# 24V_Supply.net
KiCad netlist of a schematic drawn in Altium Designer
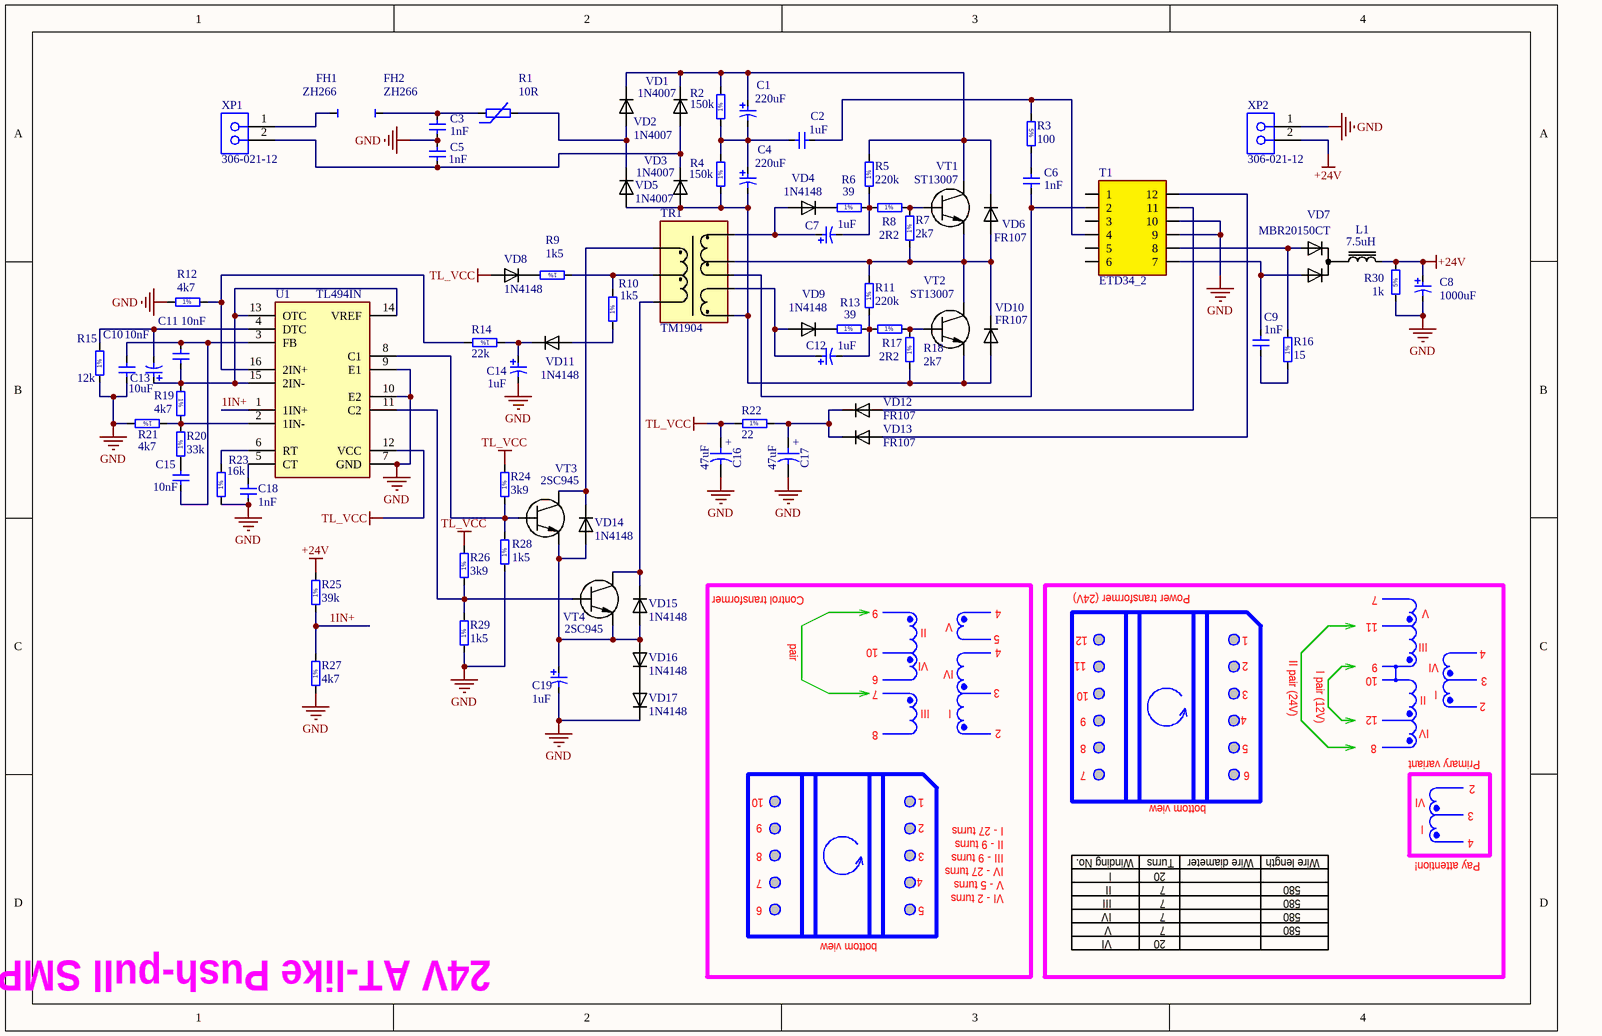
[diagram p0: 24V_Supply.SchDoc]

(export (version "E")
  (design (tool "Eeschema 10.0.6"))
  (components
    (comp (ref "C1")
      (value "220uF")
      (footprint "CAP_EL_22_25_VERT")
      (fields
        (field (name "PART NUMBER") "LG200M0220BPF-2225 (VERT MOUNTED)")
        (field (name "VOLTAGE") "200V")
      )
      (libsource (lib "Capacitor") (part "CAP_POLAR"))
    )
    (comp (ref "C2")
      (value "1uF")
      (footprint "CAPRR2000W80L2400T750H1500_CL21")
      (description "SMD 0805 Capacitor")
      (fields (field (name "PART NUMBER") "К73-17-250-1 10%") (field (name "VOLTAGE") "250V"))
      (libsource (lib "Capacitor") (part "CAP_NON_POLAR"))
    )
    (comp (ref "C3")
      (value "1nF")
      (footprint "CAP_5.0MM")
      (description "SMD 0805 Capacitor")
      (fields (field (name "PART NUMBER") "CK45-B3DD102KYNN") (field (name "VOLTAGE") "2000V"))
      (libsource (lib "Capacitor") (part "CAP_NON_POLAR"))
    )
    (comp (ref "C4")
      (value "220uF")
      (footprint "CAP_EL_22_25_VERT")
      (fields
        (field (name "PART NUMBER") "LG200M0220BPF-2225 (VERT MOUNTED)")
        (field (name "VOLTAGE") "200V")
      )
      (libsource (lib "Capacitor") (part "CAP_POLAR"))
    )
    (comp (ref "C5")
      (value "1nF")
      (footprint "CAP_5.0MM")
      (description "SMD 0805 Capacitor")
      (fields (field (name "PART NUMBER") "CK45-B3DD102KYNN") (field (name "VOLTAGE") "2000V"))
      (libsource (lib "Capacitor") (part "CAP_NON_POLAR"))
    )
    (comp (ref "C6")
      (value "1nF")
      (footprint "CAP_5.0MM")
      (description "SMD 0805 Capacitor")
      (fields (field (name "PART NUMBER") "CK45-B3DD102KYNN") (field (name "VOLTAGE") "2000V"))
      (libsource (lib "Capacitor") (part "CAP_NON_POLAR"))
    )
    (comp (ref "C7")
      (value "1uF")
      (footprint "CAP_EL_05_11_VERT")
      (fields (field (name "PART NUMBER") "SH050M1R00B2F-0511 (VERT MOUNTED)") (field (name "VOLTAGE") "50V"))
      (libsource (lib "Capacitor") (part "CAP_POLAR"))
    )
    (comp (ref "C8")
      (value "1000uF")
      (footprint "CAP_EL_13_20_VERT")
      (fields (field (name "PART NUMBER") "SK035M1000B5S-1320 (VERT MOUNTED)") (field (name "VOLTAGE") "35V"))
      (libsource (lib "Capacitor") (part "CAP_POLAR"))
    )
    (comp (ref "C9")
      (value "1nF")
      (footprint "CAP_5.0MM")
      (description "SMD 0805 Capacitor")
      (fields (field (name "PART NUMBER") "CK45-B3DD102KYNN") (field (name "VOLTAGE") "2000V"))
      (libsource (lib "Capacitor") (part "CAP_NON_POLAR"))
    )
    (comp (ref "C10")
      (value "10nF")
      (footprint "CAP_5.0MM")
      (description "SMD 0805 Capacitor")
      (fields (field (name "PART NUMBER") "TS170R1H103K8BBB0R") (field (name "VOLTAGE") "50V"))
      (libsource (lib "Capacitor") (part "CAP_NON_POLAR"))
    )
    (comp (ref "C11")
      (value "10nF")
      (footprint "CAP_5.0MM")
      (description "SMD 0805 Capacitor")
      (fields (field (name "PART NUMBER") "TS170R1H103K8BBB0R") (field (name "VOLTAGE") "50V"))
      (libsource (lib "Capacitor") (part "CAP_NON_POLAR"))
    )
    (comp (ref "C12")
      (value "1uF")
      (footprint "CAP_EL_05_11_VERT")
      (fields (field (name "PART NUMBER") "SH050M1R00B2F-0511 (VERT MOUNTED)") (field (name "VOLTAGE") "50V"))
      (libsource (lib "Capacitor") (part "CAP_POLAR"))
    )
    (comp (ref "C13")
      (value "10uF")
      (footprint "CAP_EL_05_11_VERT")
      (fields (field (name "PART NUMBER") "SH050M0010B2F-0511 (VERT MOUNTED)") (field (name "VOLTAGE") "50V"))
      (libsource (lib "Capacitor") (part "CAP_POLAR"))
    )
    (comp (ref "C14")
      (value "1uF")
      (footprint "CAP_EL_05_11_VERT")
      (fields (field (name "PART NUMBER") "SH050M1R00B2F-0511 (VERT MOUNTED)") (field (name "VOLTAGE") "50V"))
      (libsource (lib "Capacitor") (part "CAP_POLAR"))
    )
    (comp (ref "C15")
      (value "10nF")
      (footprint "CAP_5.0MM")
      (description "SMD 0805 Capacitor")
      (fields (field (name "PART NUMBER") "TS170R1H103K8BBB0R") (field (name "VOLTAGE") "50V"))
      (libsource (lib "Capacitor") (part "CAP_NON_POLAR"))
    )
    (comp (ref "C16")
      (value "47uF")
      (footprint "CAPPR250-500X1100")
      (description "Polarised capacitor")
      (fields
        (field (name "PART NUMBER") "CAER_47UF_25V_20%_250-500X1100")
        (field (name "VOLTAGE") "25V")
        (field (name "AUTHOR") "CERN DEM JLC")
      )
      (libsource (lib "Capacitors") (part "Capacitor - polarized"))
    )
    (comp (ref "C17")
      (value "47uF")
      (footprint "CAPPR250-500X1100")
      (description "Polarised capacitor")
      (fields
        (field (name "PART NUMBER") "CAER_47UF_25V_20%_250-500X1100")
        (field (name "VOLTAGE") "25V")
        (field (name "AUTHOR") "CERN DEM JLC")
      )
      (libsource (lib "Capacitors") (part "Capacitor - polarized"))
    )
    (comp (ref "C18")
      (value "1nF")
      (footprint "CAP_5.0MM")
      (description "SMD 0805 Capacitor")
      (fields (field (name "PART NUMBER") "TS170R1H102JSBNB0R") (field (name "VOLTAGE") "50V"))
      (libsource (lib "Capacitor") (part "CAP_NON_POLAR"))
    )
    (comp (ref "C19")
      (value "1uF")
      (footprint "CAP_EL_05_11_VERT")
      (fields (field (name "PART NUMBER") "SH050M1R00B2F-0511 (VERT MOUNTED)") (field (name "VOLTAGE") "50V"))
      (libsource (lib "Capacitor") (part "CAP_POLAR"))
    )
    (comp (ref "FH1") (value "ZH266") (footprint "ZH266") (libsource (lib "Connector") (part "Fuse Clip")))
    (comp (ref "FH2") (value "ZH266") (footprint "ZH266") (libsource (lib "Connector") (part "Fuse Clip")))
    (comp (ref "L1")
      (value "7.5uH")
      (footprint "DGS")
      (fields (field (name "PART NUMBER") "DGS") (field (name "TOLERANCE") "± 10%"))
      (libsource (lib "Transformer") (part "Core_Inductor"))
    )
    (comp (ref "R1")
      (value "10R")
      (footprint "B57164K")
      (fields (field (name "PART NUMBER") "B57164K"))
      (libsource (lib "Resistor") (part "Resistor - Thermo"))
    )
    (comp (ref "R2")
      (value "150k")
      (footprint "RES_AXIAL_0_25_8")
      (fields
        (field (name "PART NUMBER") "RMF_150K_1%_0.6W_50PPM_1016-630X250")
        (field (name "POWER") "0.6W")
        (field (name "TOLERANCE") "±1%")
        (field (name "AUTHOR") "CERN DEM JLC")
      )
      (libsource (lib "Resistor") (part "Resistor - 1%"))
    )
    (comp (ref "R3")
      (value "100")
      (footprint "RES_VERT_2W_5")
      (fields (field (name "PART NUMBER") "RCF_100R_5%_2W_HB"))
      (libsource (lib "Resistor") (part "Resistor - 5%"))
    )
    (comp (ref "R4")
      (value "150k")
      (footprint "RES_AXIAL_0_25_8")
      (fields
        (field (name "PART NUMBER") "RMF_150K_1%_0.6W_50PPM_1016-630X250")
        (field (name "POWER") "0.6W")
        (field (name "TOLERANCE") "±1%")
        (field (name "AUTHOR") "CERN DEM JLC")
      )
      (libsource (lib "Resistor") (part "Resistor - 1%"))
    )
    (comp (ref "R5")
      (value "220k")
      (footprint "RES_AXIAL_0_25_8")
      (fields
        (field (name "PART NUMBER") "RMF_220K_1%_0.6W_50PPM_1016-630X250")
        (field (name "POWER") "0.6W")
        (field (name "TOLERANCE") "±1%")
        (field (name "AUTHOR") "CERN DEM JLC")
      )
      (libsource (lib "Resistor") (part "Resistor - 1%"))
    )
    (comp (ref "R6")
      (value "39")
      (footprint "RES_AXIAL_0_25_8")
      (fields
        (field (name "PART NUMBER") "RMF_39R_1%_0.6W_50PPM_1016-630X250")
        (field (name "POWER") "0.6W")
        (field (name "TOLERANCE") "±1%")
        (field (name "AUTHOR") "CERN DEM JLC")
      )
      (libsource (lib "Resistor") (part "Resistor - 1%"))
    )
    (comp (ref "R7")
      (value "2k7")
      (footprint "RES_AXIAL_0_25_8")
      (fields
        (field (name "PART NUMBER") "RMF_2K7_1%_0.6W_50PPM_1016-630X250")
        (field (name "POWER") "0.6W")
        (field (name "TOLERANCE") "±1%")
        (field (name "AUTHOR") "CERN DEM JLC")
      )
      (libsource (lib "Resistor") (part "Resistor - 1%"))
    )
    (comp (ref "R8")
      (value "2R2")
      (footprint "RES_AXIAL_0_25_8")
      (fields
        (field (name "PART NUMBER") "RMF_2R2_1%_0.6W_50PPM_1016-630X250")
        (field (name "POWER") "0.6W")
        (field (name "TOLERANCE") "±1%")
        (field (name "AUTHOR") "CERN DEM JLC")
      )
      (libsource (lib "Resistor") (part "Resistor - 1%"))
    )
    (comp (ref "R9")
      (value "1k5")
      (footprint "RES_AXIAL_0_25_8")
      (fields
        (field (name "PART NUMBER") "RMF_1K5_1%_0.6W_50PPM_1016-630X250")
        (field (name "POWER") "0.6W")
        (field (name "TOLERANCE") "±1%")
        (field (name "AUTHOR") "CERN DEM JLC")
      )
      (libsource (lib "Resistor") (part "Resistor - 1%"))
    )
    (comp (ref "R10")
      (value "1k5")
      (footprint "RES_AXIAL_0_25_8")
      (fields
        (field (name "PART NUMBER") "RMF_1K5_1%_0.6W_50PPM_1016-630X250")
        (field (name "POWER") "0.6W")
        (field (name "TOLERANCE") "±1%")
        (field (name "AUTHOR") "CERN DEM JLC")
      )
      (libsource (lib "Resistor") (part "Resistor - 1%"))
    )
    (comp (ref "R11")
      (value "220k")
      (footprint "RES_AXIAL_0_25_8")
      (fields
        (field (name "PART NUMBER") "RMF_220K_1%_0.6W_50PPM_1016-630X250")
        (field (name "POWER") "0.6W")
        (field (name "TOLERANCE") "±1%")
        (field (name "AUTHOR") "CERN DEM JLC")
      )
      (libsource (lib "Resistor") (part "Resistor - 1%"))
    )
    (comp (ref "R12")
      (value "4k7")
      (footprint "RES_AXIAL_0_25_8")
      (fields
        (field (name "PART NUMBER") "RMF_4K7_1%_0.6W_50PPM_1016-630X250")
        (field (name "POWER") "0.6W")
        (field (name "TOLERANCE") "±1%")
        (field (name "AUTHOR") "CERN DEM JLC")
      )
      (libsource (lib "Resistor") (part "Resistor - 1%"))
    )
    (comp (ref "R13")
      (value "39")
      (footprint "RES_AXIAL_0_25_8")
      (fields
        (field (name "PART NUMBER") "RMF_39R_1%_0.6W_50PPM_1016-630X250")
        (field (name "POWER") "0.6W")
        (field (name "TOLERANCE") "±1%")
        (field (name "AUTHOR") "CERN DEM JLC")
      )
      (libsource (lib "Resistor") (part "Resistor - 1%"))
    )
    (comp (ref "R14")
      (value "22k")
      (footprint "RES_AXIAL_0_25_8")
      (fields
        (field (name "PART NUMBER") "RMF_22K_1%_0.6W_50PPM_1016-630X250")
        (field (name "POWER") "0.6W")
        (field (name "TOLERANCE") "±1%")
        (field (name "AUTHOR") "CERN DEM JLC")
      )
      (libsource (lib "Resistor") (part "Resistor - 1%"))
    )
    (comp (ref "R15")
      (value "12k")
      (footprint "RES_AXIAL_0_25_8")
      (fields
        (field (name "PART NUMBER") "RMF_12K_1%_0.6W_50PPM_1016-630X250")
        (field (name "POWER") "0.6W")
        (field (name "TOLERANCE") "±1%")
        (field (name "AUTHOR") "CERN DEM JLC")
      )
      (libsource (lib "Resistor") (part "Resistor - 1%"))
    )
    (comp (ref "R16")
      (value "15")
      (footprint "RES_AXIAL_0_25_8")
      (fields
        (field (name "PART NUMBER") "RMF_15R_1%_0.6W_50PPM_1016-630X250")
        (field (name "POWER") "0.6W")
        (field (name "TOLERANCE") "±1%")
        (field (name "AUTHOR") "CERN DEM JLC")
      )
      (libsource (lib "Resistor") (part "Resistor - 1%"))
    )
    (comp (ref "R17")
      (value "2R2")
      (footprint "RES_AXIAL_0_25_8")
      (fields
        (field (name "PART NUMBER") "RMF_2R2_1%_0.6W_50PPM_1016-630X250")
        (field (name "POWER") "0.6W")
        (field (name "TOLERANCE") "±1%")
        (field (name "AUTHOR") "CERN DEM JLC")
      )
      (libsource (lib "Resistor") (part "Resistor - 1%"))
    )
    (comp (ref "R18")
      (value "2k7")
      (footprint "RES_AXIAL_0_25_8")
      (fields
        (field (name "PART NUMBER") "RMF_2K7_1%_0.6W_50PPM_1016-630X250")
        (field (name "POWER") "0.6W")
        (field (name "TOLERANCE") "±1%")
        (field (name "AUTHOR") "CERN DEM JLC")
      )
      (libsource (lib "Resistor") (part "Resistor - 1%"))
    )
    (comp (ref "R19")
      (value "4k7")
      (footprint "RES_AXIAL_0_25_8")
      (fields
        (field (name "PART NUMBER") "RMF_4K7_1%_0.6W_50PPM_1016-630X250")
        (field (name "POWER") "0.6W")
        (field (name "TOLERANCE") "±1%")
        (field (name "AUTHOR") "CERN DEM JLC")
      )
      (libsource (lib "Resistor") (part "Resistor - 1%"))
    )
    (comp (ref "R20")
      (value "33k")
      (footprint "RES_AXIAL_0_25_8")
      (fields
        (field (name "PART NUMBER") "RMF_33K_1%_0.6W_50PPM_1016-630X250")
        (field (name "POWER") "0.6W")
        (field (name "TOLERANCE") "±1%")
        (field (name "AUTHOR") "CERN DEM JLC")
      )
      (libsource (lib "Resistor") (part "Resistor - 1%"))
    )
    (comp (ref "R21")
      (value "4k7")
      (footprint "RES_AXIAL_0_25_8")
      (fields
        (field (name "PART NUMBER") "RMF_4K7_1%_0.6W_50PPM_1016-630X250")
        (field (name "POWER") "0.6W")
        (field (name "TOLERANCE") "±1%")
        (field (name "AUTHOR") "CERN DEM JLC")
      )
      (libsource (lib "Resistor") (part "Resistor - 1%"))
    )
    (comp (ref "R22")
      (value "22")
      (footprint "RES_AXIAL_0_25_8")
      (fields
        (field (name "PART NUMBER") "RMF_22R_1%_0.6W_50PPM_1016-630X250")
        (field (name "POWER") "0.6W")
        (field (name "TOLERANCE") "±1%")
        (field (name "AUTHOR") "CERN DEM JLC")
      )
      (libsource (lib "Resistor") (part "Resistor - 1%"))
    )
    (comp (ref "R23")
      (value "16k")
      (footprint "RES_AXIAL_0_25_8")
      (fields
        (field (name "PART NUMBER") "RMF_16K_1%_0.6W_50PPM_1016-630X250")
        (field (name "POWER") "0.6W")
        (field (name "TOLERANCE") "±1%")
        (field (name "AUTHOR") "CERN DEM JLC")
      )
      (libsource (lib "Resistor") (part "Resistor - 1%"))
    )
    (comp (ref "R24")
      (value "3k9")
      (footprint "RES_AXIAL_0_25_8")
      (fields
        (field (name "PART NUMBER") "RMF_3K9_1%_0.6W_50PPM_1016-630X250")
        (field (name "POWER") "0.6W")
        (field (name "TOLERANCE") "±1%")
        (field (name "AUTHOR") "CERN DEM JLC")
      )
      (libsource (lib "Resistor") (part "Resistor - 1%"))
    )
    (comp (ref "R25")
      (value "39k")
      (footprint "RES_AXIAL_0_25_8")
      (fields
        (field (name "PART NUMBER") "RMF_22K_1%_0.6W_50PPM_1016-630X250")
        (field (name "POWER") "0.6W")
        (field (name "TOLERANCE") "±1%")
        (field (name "AUTHOR") "CERN DEM JLC")
      )
      (libsource (lib "Resistor") (part "Resistor - 1%"))
    )
    (comp (ref "R26")
      (value "3k9")
      (footprint "RES_AXIAL_0_25_8")
      (fields
        (field (name "PART NUMBER") "RMF_3K9_1%_0.6W_50PPM_1016-630X250")
        (field (name "POWER") "0.6W")
        (field (name "TOLERANCE") "±1%")
        (field (name "AUTHOR") "CERN DEM JLC")
      )
      (libsource (lib "Resistor") (part "Resistor - 1%"))
    )
    (comp (ref "R27")
      (value "4k7")
      (footprint "RES_AXIAL_0_25_8")
      (fields
        (field (name "PART NUMBER") "RMF_4K7_1%_0.6W_50PPM_1016-630X250")
        (field (name "POWER") "0.6W")
        (field (name "TOLERANCE") "±1%")
        (field (name "AUTHOR") "CERN DEM JLC")
      )
      (libsource (lib "Resistor") (part "Resistor - 1%"))
    )
    (comp (ref "R28")
      (value "1k5")
      (footprint "RES_AXIAL_0_25_8")
      (fields
        (field (name "PART NUMBER") "RMF_1K5_1%_0.6W_50PPM_1016-630X250")
        (field (name "POWER") "0.6W")
        (field (name "TOLERANCE") "±1%")
        (field (name "AUTHOR") "CERN DEM JLC")
      )
      (libsource (lib "Resistor") (part "Resistor - 1%"))
    )
    (comp (ref "R29")
      (value "1k5")
      (footprint "RES_AXIAL_0_25_8")
      (fields
        (field (name "PART NUMBER") "RMF_1K5_1%_0.6W_50PPM_1016-630X250")
        (field (name "POWER") "0.6W")
        (field (name "TOLERANCE") "±1%")
        (field (name "AUTHOR") "CERN DEM JLC")
      )
      (libsource (lib "Resistor") (part "Resistor - 1%"))
    )
    (comp (ref "R30")
      (value "1k")
      (footprint "RES_VERT_2W_5")
      (fields (field (name "PART NUMBER") "RCF_100R_5%_2W_HB"))
      (libsource (lib "Resistor") (part "Resistor - 5%"))
    )
    (comp (ref "T1")
      (value "ETD34_2")
      (footprint "ETD34_2")
      (fields (field (name "PART NUMBER") "ETD34/2"))
      (libsource (lib "Transformer") (part "Coil_Former_12pin"))
    )
    (comp (ref "TR1") (value "TM1904") (footprint "TM1904") (libsource (lib "Transformer") (part "TM1904")))
    (comp (ref "U1")
      (value "TL494IN")
      (footprint "DIP16")
      (libsource (lib "IC And Semiconductor") (part "TL494"))
    )
    (comp (ref "VD1")
      (value "1N4007")
      (footprint "DO-41")
      (fields (field (name "PART NUMBER") "1N4007_HOR"))
      (libsource (lib "IC And Semiconductor") (part "Diode - General"))
    )
    (comp (ref "VD2")
      (value "1N4007")
      (footprint "DO-41")
      (fields (field (name "PART NUMBER") "1N4007_HOR"))
      (libsource (lib "IC And Semiconductor") (part "Diode - General"))
    )
    (comp (ref "VD3")
      (value "1N4007")
      (footprint "DO-41")
      (fields (field (name "PART NUMBER") "1N4007_HOR"))
      (libsource (lib "IC And Semiconductor") (part "Diode - General"))
    )
    (comp (ref "VD4")
      (value "1N4148")
      (footprint "DO-35(300mil)")
      (fields (field (name "PART NUMBER") "1N4148 (300mil)"))
      (libsource (lib "IC And Semiconductor") (part "Diode - General"))
    )
    (comp (ref "VD5")
      (value "1N4007")
      (footprint "DO-41")
      (fields (field (name "PART NUMBER") "1N4007_HOR"))
      (libsource (lib "IC And Semiconductor") (part "Diode - General"))
    )
    (comp (ref "VD6")
      (value "FR107")
      (footprint "DO-41")
      (fields (field (name "PART NUMBER") "FR107 (HOR MOUNTED)"))
      (libsource (lib "IC And Semiconductor") (part "Diode - General"))
    )
    (comp (ref "VD7")
      (value "MBR20150CT")
      (footprint "TO-220-3")
      (libsource (lib "IC And Semiconductor") (part "D_3P_TO220"))
    )
    (comp (ref "VD8")
      (value "1N4148")
      (footprint "DO-35(300mil)")
      (fields (field (name "PART NUMBER") "1N4148 (300mil)"))
      (libsource (lib "IC And Semiconductor") (part "Diode - General"))
    )
    (comp (ref "VD9")
      (value "1N4148")
      (footprint "DO-35(300mil)")
      (fields (field (name "PART NUMBER") "1N4148 (300mil)"))
      (libsource (lib "IC And Semiconductor") (part "Diode - General"))
    )
    (comp (ref "VD10")
      (value "FR107")
      (footprint "DO-41")
      (fields (field (name "PART NUMBER") "FR107 (HOR MOUNTED)"))
      (libsource (lib "IC And Semiconductor") (part "Diode - General"))
    )
    (comp (ref "VD11")
      (value "1N4148")
      (footprint "DO-35")
      (libsource (lib "IC And Semiconductor") (part "Diode - General"))
    )
    (comp (ref "VD12")
      (value "FR107")
      (footprint "DO-41 (8.5mm)")
      (fields (field (name "PART NUMBER") "FR107 (HOR MOUNTED)"))
      (libsource (lib "IC And Semiconductor") (part "Diode - General"))
    )
    (comp (ref "VD13")
      (value "FR107")
      (footprint "DO-41 (8.5mm)")
      (fields (field (name "PART NUMBER") "FR107 (HOR MOUNTED)"))
      (libsource (lib "IC And Semiconductor") (part "Diode - General"))
    )
    (comp (ref "VD14")
      (value "1N4148")
      (footprint "DO-35")
      (libsource (lib "IC And Semiconductor") (part "Diode - General"))
    )
    (comp (ref "VD15")
      (value "1N4148")
      (footprint "DO-35")
      (libsource (lib "IC And Semiconductor") (part "Diode - General"))
    )
    (comp (ref "VD16")
      (value "1N4148")
      (footprint "DO-35")
      (libsource (lib "IC And Semiconductor") (part "Diode - General"))
    )
    (comp (ref "VD17")
      (value "1N4148")
      (footprint "DO-35")
      (libsource (lib "IC And Semiconductor") (part "Diode - General"))
    )
    (comp (ref "VT1")
      (value "ST13007")
      (footprint "TO-220-3")
      (fields (field (name "AUTHOR") "I. Kuznetsov"))
      (libsource (lib "IC And Semiconductor") (part "NPN_BIPOLAR_TO92"))
    )
    (comp (ref "VT2")
      (value "ST13007")
      (footprint "TO-220-3")
      (fields (field (name "AUTHOR") "I. Kuznetsov"))
      (libsource (lib "IC And Semiconductor") (part "NPN_BIPOLAR_TO92"))
    )
    (comp (ref "VT3")
      (value "2SC945")
      (footprint "TO92")
      (libsource (lib "IC And Semiconductor") (part "NPN_BIPOLAR_TO92"))
    )
    (comp (ref "VT4")
      (value "2SC945")
      (footprint "TO92")
      (libsource (lib "IC And Semiconductor") (part "NPN_BIPOLAR_TO92"))
    )
    (comp (ref "XP1")
      (value "306-021-12")
      (footprint "306-021-12")
      (libsource (lib "Connector") (part "CN_02S_1W"))
    )
    (comp (ref "XP2")
      (value "306-021-12")
      (footprint "306-021-12")
      (libsource (lib "Connector") (part "CN_02S_1W"))
    )
  )
  (nets
    (net (code "1") (name "+24V") (class "Default")
      (node (ref "C8") (pin "1") (pinfunction "1_1") (pintype "passive"))
      (node (ref "L1") (pin "2") (pinfunction "2_2") (pintype "passive"))
      (node (ref "R25") (pin "2") (pinfunction "2_2") (pintype "passive"))
      (node (ref "R30") (pin "2") (pinfunction "2_2") (pintype "passive"))
      (node (ref "XP2") (pin "2") (pinfunction "2_2") (pintype "passive"))
    )
    (net (code "2") (name "/1IN+") (class "Default")
      (node (ref "R25") (pin "1") (pinfunction "1_1") (pintype "passive"))
      (node (ref "R27") (pin "2") (pinfunction "2_2") (pintype "passive"))
      (node (ref "U1") (pin "1") (pinfunction "1IN+_1") (pintype "passive"))
    )
    (net (code "3") (name "GND") (class "Default")
      (node (ref "C10") (pin "1") (pinfunction "1_1") (pintype "passive"))
      (node (ref "C14") (pin "2") (pinfunction "2_2") (pintype "passive"))
      (node (ref "C16") (pin "2") (pinfunction "2_2") (pintype "passive"))
      (node (ref "C17") (pin "2") (pinfunction "2_2") (pintype "passive"))
      (node (ref "C18") (pin "1") (pinfunction "1_1") (pintype "passive"))
      (node (ref "C19") (pin "2") (pinfunction "2_2") (pintype "passive"))
      (node (ref "C3") (pin "1") (pinfunction "1_1") (pintype "passive"))
      (node (ref "C5") (pin "2") (pinfunction "2_2") (pintype "passive"))
      (node (ref "C8") (pin "2") (pinfunction "2_2") (pintype "passive"))
      (node (ref "R12") (pin "1") (pinfunction "1_1") (pintype "passive"))
      (node (ref "R15") (pin "1") (pinfunction "1_1") (pintype "passive"))
      (node (ref "R21") (pin "2") (pinfunction "2_2") (pintype "passive"))
      (node (ref "R23") (pin "1") (pinfunction "1_1") (pintype "passive"))
      (node (ref "R27") (pin "1") (pinfunction "1_1") (pintype "passive"))
      (node (ref "R28") (pin "1") (pinfunction "1_1") (pintype "passive"))
      (node (ref "R29") (pin "1") (pinfunction "1_1") (pintype "passive"))
      (node (ref "R30") (pin "1") (pinfunction "1_1") (pintype "passive"))
      (node (ref "T1") (pin "10") (pinfunction "10_10") (pintype "passive"))
      (node (ref "T1") (pin "9") (pinfunction "9_9") (pintype "passive"))
      (node (ref "U1") (pin "10") (pinfunction "E2_10") (pintype "passive"))
      (node (ref "U1") (pin "7") (pinfunction "GND_7") (pintype "passive"))
      (node (ref "U1") (pin "9") (pinfunction "E1_9") (pintype "passive"))
      (node (ref "VD17") (pin "K") (pinfunction "K_K") (pintype "passive"))
      (node (ref "XP2") (pin "1") (pinfunction "1_1") (pintype "passive"))
    )
    (net (code "4") (name "Net-(C1-Pad2)") (class "Default")
      (node (ref "C1") (pin "2") (pinfunction "2_2") (pintype "passive"))
      (node (ref "C2") (pin "1") (pinfunction "1_1") (pintype "passive"))
      (node (ref "C4") (pin "1") (pinfunction "1_1") (pintype "passive"))
      (node (ref "R2") (pin "1") (pinfunction "1_1") (pintype "passive"))
      (node (ref "R4") (pin "2") (pinfunction "2_2") (pintype "passive"))
    )
    (net (code "5") (name "Net-(C2-Pad2)") (class "Default")
      (node (ref "C2") (pin "2") (pinfunction "2_2") (pintype "passive"))
      (node (ref "R3") (pin "1") (pinfunction "1_1") (pintype "passive"))
      (node (ref "T1") (pin "4") (pinfunction "4_4") (pintype "passive"))
    )
    (net (code "6") (name "Net-(C3-Pad2)") (class "Default")
      (node (ref "C3") (pin "2") (pinfunction "2_2") (pintype "passive"))
      (node (ref "FH2") (pin "1") (pinfunction "1_1") (pintype "passive"))
      (node (ref "R1") (pin "1") (pinfunction "1_1") (pintype "passive"))
    )
    (net (code "7") (name "Net-(C5-Pad1)") (class "Default")
      (node (ref "C5") (pin "1") (pinfunction "1_1") (pintype "passive"))
      (node (ref "VD1") (pin "A") (pinfunction "A_A") (pintype "passive"))
      (node (ref "VD3") (pin "K") (pinfunction "K_K") (pintype "passive"))
      (node (ref "XP1") (pin "2") (pinfunction "2_2") (pintype "passive"))
    )
    (net (code "8") (name "Net-(C6-Pad1)") (class "Default")
      (node (ref "C6") (pin "1") (pinfunction "1_1") (pintype "passive"))
      (node (ref "T1") (pin "2") (pinfunction "2_2") (pintype "passive"))
      (node (ref "TR1") (pin "6") (pinfunction "6_6") (pintype "passive"))
    )
    (net (code "9") (name "Net-(C6-Pad2)") (class "Default")
      (node (ref "C6") (pin "2") (pinfunction "2_2") (pintype "passive"))
      (node (ref "R3") (pin "2") (pinfunction "2_2") (pintype "passive"))
    )
    (net (code "10") (name "Net-(C7-Pad1)") (class "Default")
      (node (ref "C7") (pin "1") (pinfunction "1_1") (pintype "passive"))
      (node (ref "TR1") (pin "9") (pinfunction "9_9") (pintype "passive"))
      (node (ref "VD4") (pin "A") (pinfunction "A_A") (pintype "passive"))
    )
    (net (code "11") (name "Net-(C7-Pad2)") (class "Default")
      (node (ref "C7") (pin "2") (pinfunction "2_2") (pintype "passive"))
      (node (ref "R5") (pin "1") (pinfunction "1_1") (pintype "passive"))
      (node (ref "R6") (pin "2") (pinfunction "2_2") (pintype "passive"))
      (node (ref "R8") (pin "1") (pinfunction "1_1") (pintype "passive"))
    )
    (net (code "12") (name "Net-(C9-Pad1)") (class "Default")
      (node (ref "C9") (pin "1") (pinfunction "1_1") (pintype "passive"))
      (node (ref "R16") (pin "1") (pinfunction "1_1") (pintype "passive"))
    )
    (net (code "13") (name "Net-(C9-Pad2)") (class "Default")
      (node (ref "C9") (pin "2") (pinfunction "2_2") (pintype "passive"))
      (node (ref "T1") (pin "7") (pinfunction "7_7") (pintype "passive"))
      (node (ref "VD7") (pin "1") (pinfunction "A_1") (pintype "passive"))
    )
    (net (code "14") (name "Net-(C12-Pad1)") (class "Default")
      (node (ref "C12") (pin "1") (pinfunction "1_1") (pintype "passive"))
      (node (ref "TR1") (pin "8") (pinfunction "8_8") (pintype "passive"))
      (node (ref "VD9") (pin "A") (pinfunction "A_A") (pintype "passive"))
    )
    (net (code "15") (name "Net-(C12-Pad2)") (class "Default")
      (node (ref "C12") (pin "2") (pinfunction "2_2") (pintype "passive"))
      (node (ref "R11") (pin "1") (pinfunction "1_1") (pintype "passive"))
      (node (ref "R13") (pin "2") (pinfunction "2_2") (pintype "passive"))
      (node (ref "R17") (pin "1") (pinfunction "1_1") (pintype "passive"))
    )
    (net (code "16") (name "Net-(C14-Pad1)") (class "Default")
      (node (ref "C14") (pin "1") (pinfunction "1_1") (pintype "passive"))
      (node (ref "R14") (pin "1") (pinfunction "1_1") (pintype "passive"))
      (node (ref "VD11") (pin "K") (pinfunction "K_K") (pintype "passive"))
    )
    (net (code "17") (name "Net-(C15-Pad2)") (class "Default")
      (node (ref "C15") (pin "2") (pinfunction "2_2") (pintype "passive"))
      (node (ref "R20") (pin "1") (pinfunction "1_1") (pintype "passive"))
    )
    (net (code "18") (name "Net-(C17-Pad1)") (class "Default")
      (node (ref "C17") (pin "1") (pinfunction "1_1") (pintype "passive"))
      (node (ref "R22") (pin "2") (pinfunction "2_2") (pintype "passive"))
      (node (ref "VD12") (pin "K") (pinfunction "K_K") (pintype "passive"))
      (node (ref "VD13") (pin "K") (pinfunction "K_K") (pintype "passive"))
    )
    (net (code "19") (name "Net-(FH1-Pad1)") (class "Default")
      (node (ref "FH1") (pin "1") (pinfunction "1_1") (pintype "passive"))
      (node (ref "XP1") (pin "1") (pinfunction "1_1") (pintype "passive"))
    )
    (net (code "20") (name "Net-(R1-Pad2)") (class "Default")
      (node (ref "R1") (pin "2") (pinfunction "2_2") (pintype "passive"))
      (node (ref "VD2") (pin "A") (pinfunction "A_A") (pintype "passive"))
      (node (ref "VD5") (pin "K") (pinfunction "K_K") (pintype "passive"))
    )
    (net (code "21") (name "Net-(R6-Pad1)") (class "Default")
      (node (ref "R6") (pin "1") (pinfunction "1_1") (pintype "passive"))
      (node (ref "VD4") (pin "K") (pinfunction "K_K") (pintype "passive"))
    )
    (net (code "22") (name "Net-(R9-Pad2)") (class "Default")
      (node (ref "R9") (pin "2") (pinfunction "2_2") (pintype "passive"))
      (node (ref "VD8") (pin "K") (pinfunction "K_K") (pintype "passive"))
    )
    (net (code "23") (name "Net-(R10-Pad1)") (class "Default")
      (node (ref "R10") (pin "1") (pinfunction "1_1") (pintype "passive"))
      (node (ref "VD11") (pin "A") (pinfunction "A_A") (pintype "passive"))
    )
    (net (code "24") (name "Net-(R10-Pad2)") (class "Default")
      (node (ref "R10") (pin "2") (pinfunction "2_2") (pintype "passive"))
      (node (ref "R9") (pin "1") (pinfunction "1_1") (pintype "passive"))
      (node (ref "TR1") (pin "3") (pinfunction "3_3") (pintype "passive"))
    )
    (net (code "25") (name "Net-(R13-Pad1)") (class "Default")
      (node (ref "R13") (pin "1") (pinfunction "1_1") (pintype "passive"))
      (node (ref "VD9") (pin "K") (pinfunction "K_K") (pintype "passive"))
    )
    (net (code "26") (name "Net-(R16-Pad2)") (class "Default")
      (node (ref "R16") (pin "2") (pinfunction "2_2") (pintype "passive"))
      (node (ref "T1") (pin "8") (pinfunction "8_8") (pintype "passive"))
      (node (ref "VD7") (pin "3") (pinfunction "A_3") (pintype "passive"))
    )
    (net (code "27") (name "Net-(T1-Pad11)") (class "Default")
      (node (ref "T1") (pin "11") (pinfunction "11_11") (pintype "passive"))
      (node (ref "VD12") (pin "A") (pinfunction "A_A") (pintype "passive"))
    )
    (net (code "28") (name "Net-(T1-Pad12)") (class "Default")
      (node (ref "T1") (pin "12") (pinfunction "12_12") (pintype "passive"))
      (node (ref "VD13") (pin "A") (pinfunction "A_A") (pintype "passive"))
    )
    (net (code "29") (name "Net-(U1-1IN-)") (class "Default")
      (node (ref "R19") (pin "2") (pinfunction "2_2") (pintype "passive"))
      (node (ref "R20") (pin "2") (pinfunction "2_2") (pintype "passive"))
      (node (ref "R21") (pin "1") (pinfunction "1_1") (pintype "passive"))
      (node (ref "U1") (pin "2") (pinfunction "1IN-_2") (pintype "passive"))
    )
    (net (code "30") (name "Net-(U1-2IN+)") (class "Default")
      (node (ref "R12") (pin "2") (pinfunction "2_2") (pintype "passive"))
      (node (ref "R14") (pin "2") (pinfunction "2_2") (pintype "passive"))
      (node (ref "U1") (pin "16") (pinfunction "2IN+_16") (pintype "passive"))
    )
    (net (code "31") (name "Net-(U1-2IN-)") (class "Default")
      (node (ref "C11") (pin "1") (pinfunction "1_1") (pintype "passive"))
      (node (ref "C13") (pin "1") (pinfunction "1_1") (pintype "passive"))
      (node (ref "R19") (pin "1") (pinfunction "1_1") (pintype "passive"))
      (node (ref "U1") (pin "13") (pinfunction "OTC_13") (pintype "passive"))
      (node (ref "U1") (pin "14") (pinfunction "VREF_14") (pintype "passive"))
      (node (ref "U1") (pin "15") (pinfunction "2IN-_15") (pintype "passive"))
    )
    (net (code "32") (name "Net-(U1-C1)") (class "Default")
      (node (ref "R24") (pin "1") (pinfunction "1_1") (pintype "passive"))
      (node (ref "R28") (pin "2") (pinfunction "2_2") (pintype "passive"))
      (node (ref "U1") (pin "8") (pinfunction "C1_8") (pintype "passive"))
      (node (ref "VT3") (pin "1") (pinfunction "B_1") (pintype "passive"))
    )
    (net (code "33") (name "Net-(U1-C2)") (class "Default")
      (node (ref "R26") (pin "1") (pinfunction "1_1") (pintype "passive"))
      (node (ref "R29") (pin "2") (pinfunction "2_2") (pintype "passive"))
      (node (ref "U1") (pin "11") (pinfunction "C2_11") (pintype "passive"))
      (node (ref "VT4") (pin "1") (pinfunction "B_1") (pintype "passive"))
    )
    (net (code "34") (name "Net-(U1-CT)") (class "Default")
      (node (ref "C18") (pin "2") (pinfunction "2_2") (pintype "passive"))
      (node (ref "U1") (pin "5") (pinfunction "CT_5") (pintype "passive"))
    )
    (net (code "35") (name "Net-(U1-DTC)") (class "Default")
      (node (ref "C13") (pin "2") (pinfunction "2_2") (pintype "passive"))
      (node (ref "R15") (pin "2") (pinfunction "2_2") (pintype "passive"))
      (node (ref "U1") (pin "4") (pinfunction "DTC_4") (pintype "passive"))
    )
    (net (code "36") (name "Net-(U1-FB)") (class "Default")
      (node (ref "C10") (pin "2") (pinfunction "2_2") (pintype "passive"))
      (node (ref "C11") (pin "2") (pinfunction "2_2") (pintype "passive"))
      (node (ref "C15") (pin "1") (pinfunction "1_1") (pintype "passive"))
      (node (ref "U1") (pin "3") (pinfunction "FB_3") (pintype "passive"))
    )
    (net (code "37") (name "Net-(U1-RT)") (class "Default")
      (node (ref "R23") (pin "2") (pinfunction "2_2") (pintype "passive"))
      (node (ref "U1") (pin "6") (pinfunction "RT_6") (pintype "passive"))
    )
    (net (code "38") (name "Net-(VD7-K)") (class "Default")
      (node (ref "L1") (pin "1") (pinfunction "1_1") (pintype "passive"))
      (node (ref "VD7") (pin "2") (pinfunction "K_2") (pintype "passive"))
    )
    (net (code "39") (name "Net-(VD16-PadK)") (class "Default")
      (node (ref "VD16") (pin "K") (pinfunction "K_K") (pintype "passive"))
      (node (ref "VD17") (pin "A") (pinfunction "A_A") (pintype "passive"))
    )
    (net (code "40") (name "Net-(VT1-B)") (class "Default")
      (node (ref "R7") (pin "2") (pinfunction "2_2") (pintype "passive"))
      (node (ref "R8") (pin "2") (pinfunction "2_2") (pintype "passive"))
      (node (ref "VT1") (pin "1") (pinfunction "B_1") (pintype "passive"))
    )
    (net (code "41") (name "Net-(VT1-C)") (class "Default")
      (node (ref "C1") (pin "1") (pinfunction "1_1") (pintype "passive"))
      (node (ref "R2") (pin "2") (pinfunction "2_2") (pintype "passive"))
      (node (ref "R5") (pin "2") (pinfunction "2_2") (pintype "passive"))
      (node (ref "VD1") (pin "K") (pinfunction "K_K") (pintype "passive"))
      (node (ref "VD2") (pin "K") (pinfunction "K_K") (pintype "passive"))
      (node (ref "VD6") (pin "K") (pinfunction "K_K") (pintype "passive"))
      (node (ref "VT1") (pin "2") (pinfunction "C_2") (pintype "passive"))
    )
    (net (code "42") (name "Net-(VT1-E)") (class "Default")
      (node (ref "R11") (pin "2") (pinfunction "2_2") (pintype "passive"))
      (node (ref "R7") (pin "1") (pinfunction "1_1") (pintype "passive"))
      (node (ref "TR1") (pin "10") (pinfunction "10_10") (pintype "passive"))
      (node (ref "VD10") (pin "K") (pinfunction "K_K") (pintype "passive"))
      (node (ref "VD6") (pin "A") (pinfunction "A_A") (pintype "passive"))
      (node (ref "VT1") (pin "3") (pinfunction "E_3") (pintype "passive"))
      (node (ref "VT2") (pin "2") (pinfunction "C_2") (pintype "passive"))
    )
    (net (code "43") (name "Net-(VT2-B)") (class "Default")
      (node (ref "R17") (pin "2") (pinfunction "2_2") (pintype "passive"))
      (node (ref "R18") (pin "2") (pinfunction "2_2") (pintype "passive"))
      (node (ref "VT2") (pin "1") (pinfunction "B_1") (pintype "passive"))
    )
    (net (code "44") (name "Net-(VT2-E)") (class "Default")
      (node (ref "C4") (pin "2") (pinfunction "2_2") (pintype "passive"))
      (node (ref "R18") (pin "1") (pinfunction "1_1") (pintype "passive"))
      (node (ref "R4") (pin "1") (pinfunction "1_1") (pintype "passive"))
      (node (ref "TR1") (pin "7") (pinfunction "7_7") (pintype "passive"))
      (node (ref "VD10") (pin "A") (pinfunction "A_A") (pintype "passive"))
      (node (ref "VD3") (pin "A") (pinfunction "A_A") (pintype "passive"))
      (node (ref "VD5") (pin "A") (pinfunction "A_A") (pintype "passive"))
      (node (ref "VT2") (pin "3") (pinfunction "E_3") (pintype "passive"))
    )
    (net (code "45") (name "Net-(VT3-C)") (class "Default")
      (node (ref "TR1") (pin "4") (pinfunction "4_4") (pintype "passive"))
      (node (ref "VD14") (pin "K") (pinfunction "K_K") (pintype "passive"))
      (node (ref "VT3") (pin "2") (pinfunction "C_2") (pintype "passive"))
    )
    (net (code "46") (name "Net-(VT3-E)") (class "Default")
      (node (ref "C19") (pin "1") (pinfunction "1_1") (pintype "passive"))
      (node (ref "VD14") (pin "A") (pinfunction "A_A") (pintype "passive"))
      (node (ref "VD15") (pin "A") (pinfunction "A_A") (pintype "passive"))
      (node (ref "VD16") (pin "A") (pinfunction "A_A") (pintype "passive"))
      (node (ref "VT3") (pin "3") (pinfunction "E_3") (pintype "passive"))
      (node (ref "VT4") (pin "3") (pinfunction "E_3") (pintype "passive"))
    )
    (net (code "47") (name "Net-(VT4-C)") (class "Default")
      (node (ref "TR1") (pin "2") (pinfunction "2_2") (pintype "passive"))
      (node (ref "VD15") (pin "K") (pinfunction "K_K") (pintype "passive"))
      (node (ref "VT4") (pin "2") (pinfunction "C_2") (pintype "passive"))
    )
    (net (code "48") (name "TL_VCC") (class "Default")
      (node (ref "C16") (pin "1") (pinfunction "1_1") (pintype "passive"))
      (node (ref "R22") (pin "1") (pinfunction "1_1") (pintype "passive"))
      (node (ref "R24") (pin "2") (pinfunction "2_2") (pintype "passive"))
      (node (ref "R26") (pin "2") (pinfunction "2_2") (pintype "passive"))
      (node (ref "U1") (pin "12") (pinfunction "VCC_12") (pintype "passive"))
      (node (ref "VD8") (pin "A") (pinfunction "A_A") (pintype "passive"))
    )
    (net (code "49") (name "unconnected-(T1-Pad1)") (class "Default")
      (node (ref "T1") (pin "1") (pinfunction "1_1") (pintype "passive"))
    )
    (net (code "50") (name "unconnected-(T1-Pad3)") (class "Default")
      (node (ref "T1") (pin "3") (pinfunction "3_3") (pintype "passive"))
    )
    (net (code "51") (name "unconnected-(T1-Pad5)") (class "Default")
      (node (ref "T1") (pin "5") (pinfunction "5_5") (pintype "passive"))
    )
    (net (code "52") (name "unconnected-(T1-Pad6)") (class "Default")
      (node (ref "T1") (pin "6") (pinfunction "6_6") (pintype "passive"))
    )
  )
)
